# tello-encoder-generic-DaisyChain.net
KiCad netlist of a schematic drawn in EAGLE
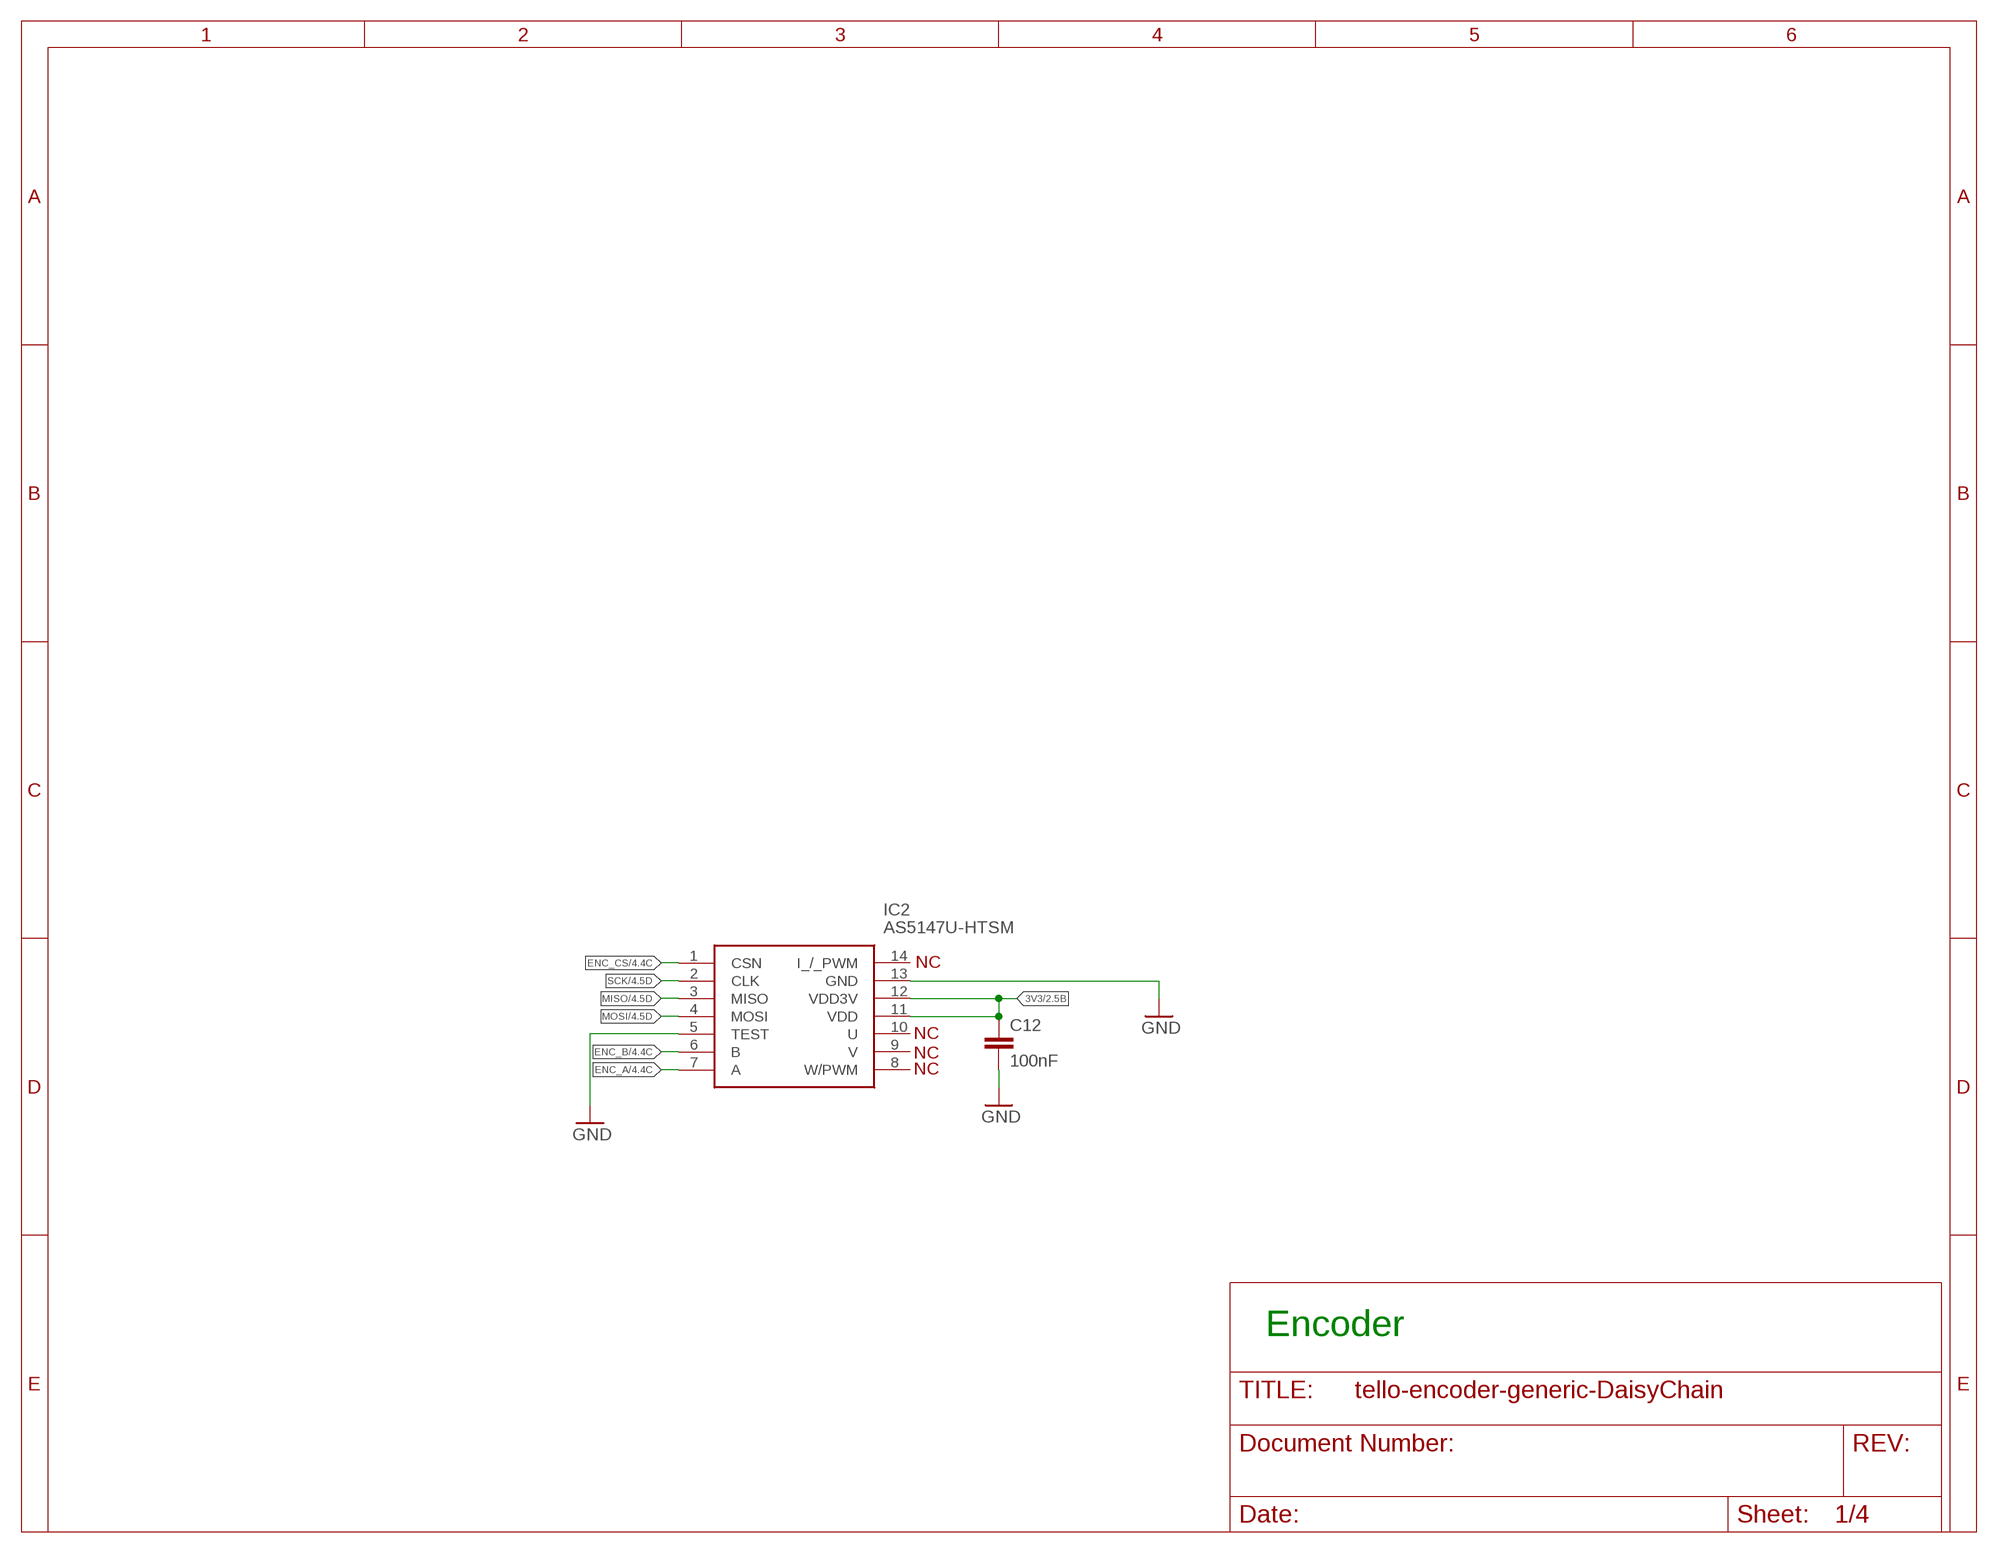
[diagram p0: schematic, sheet 1]
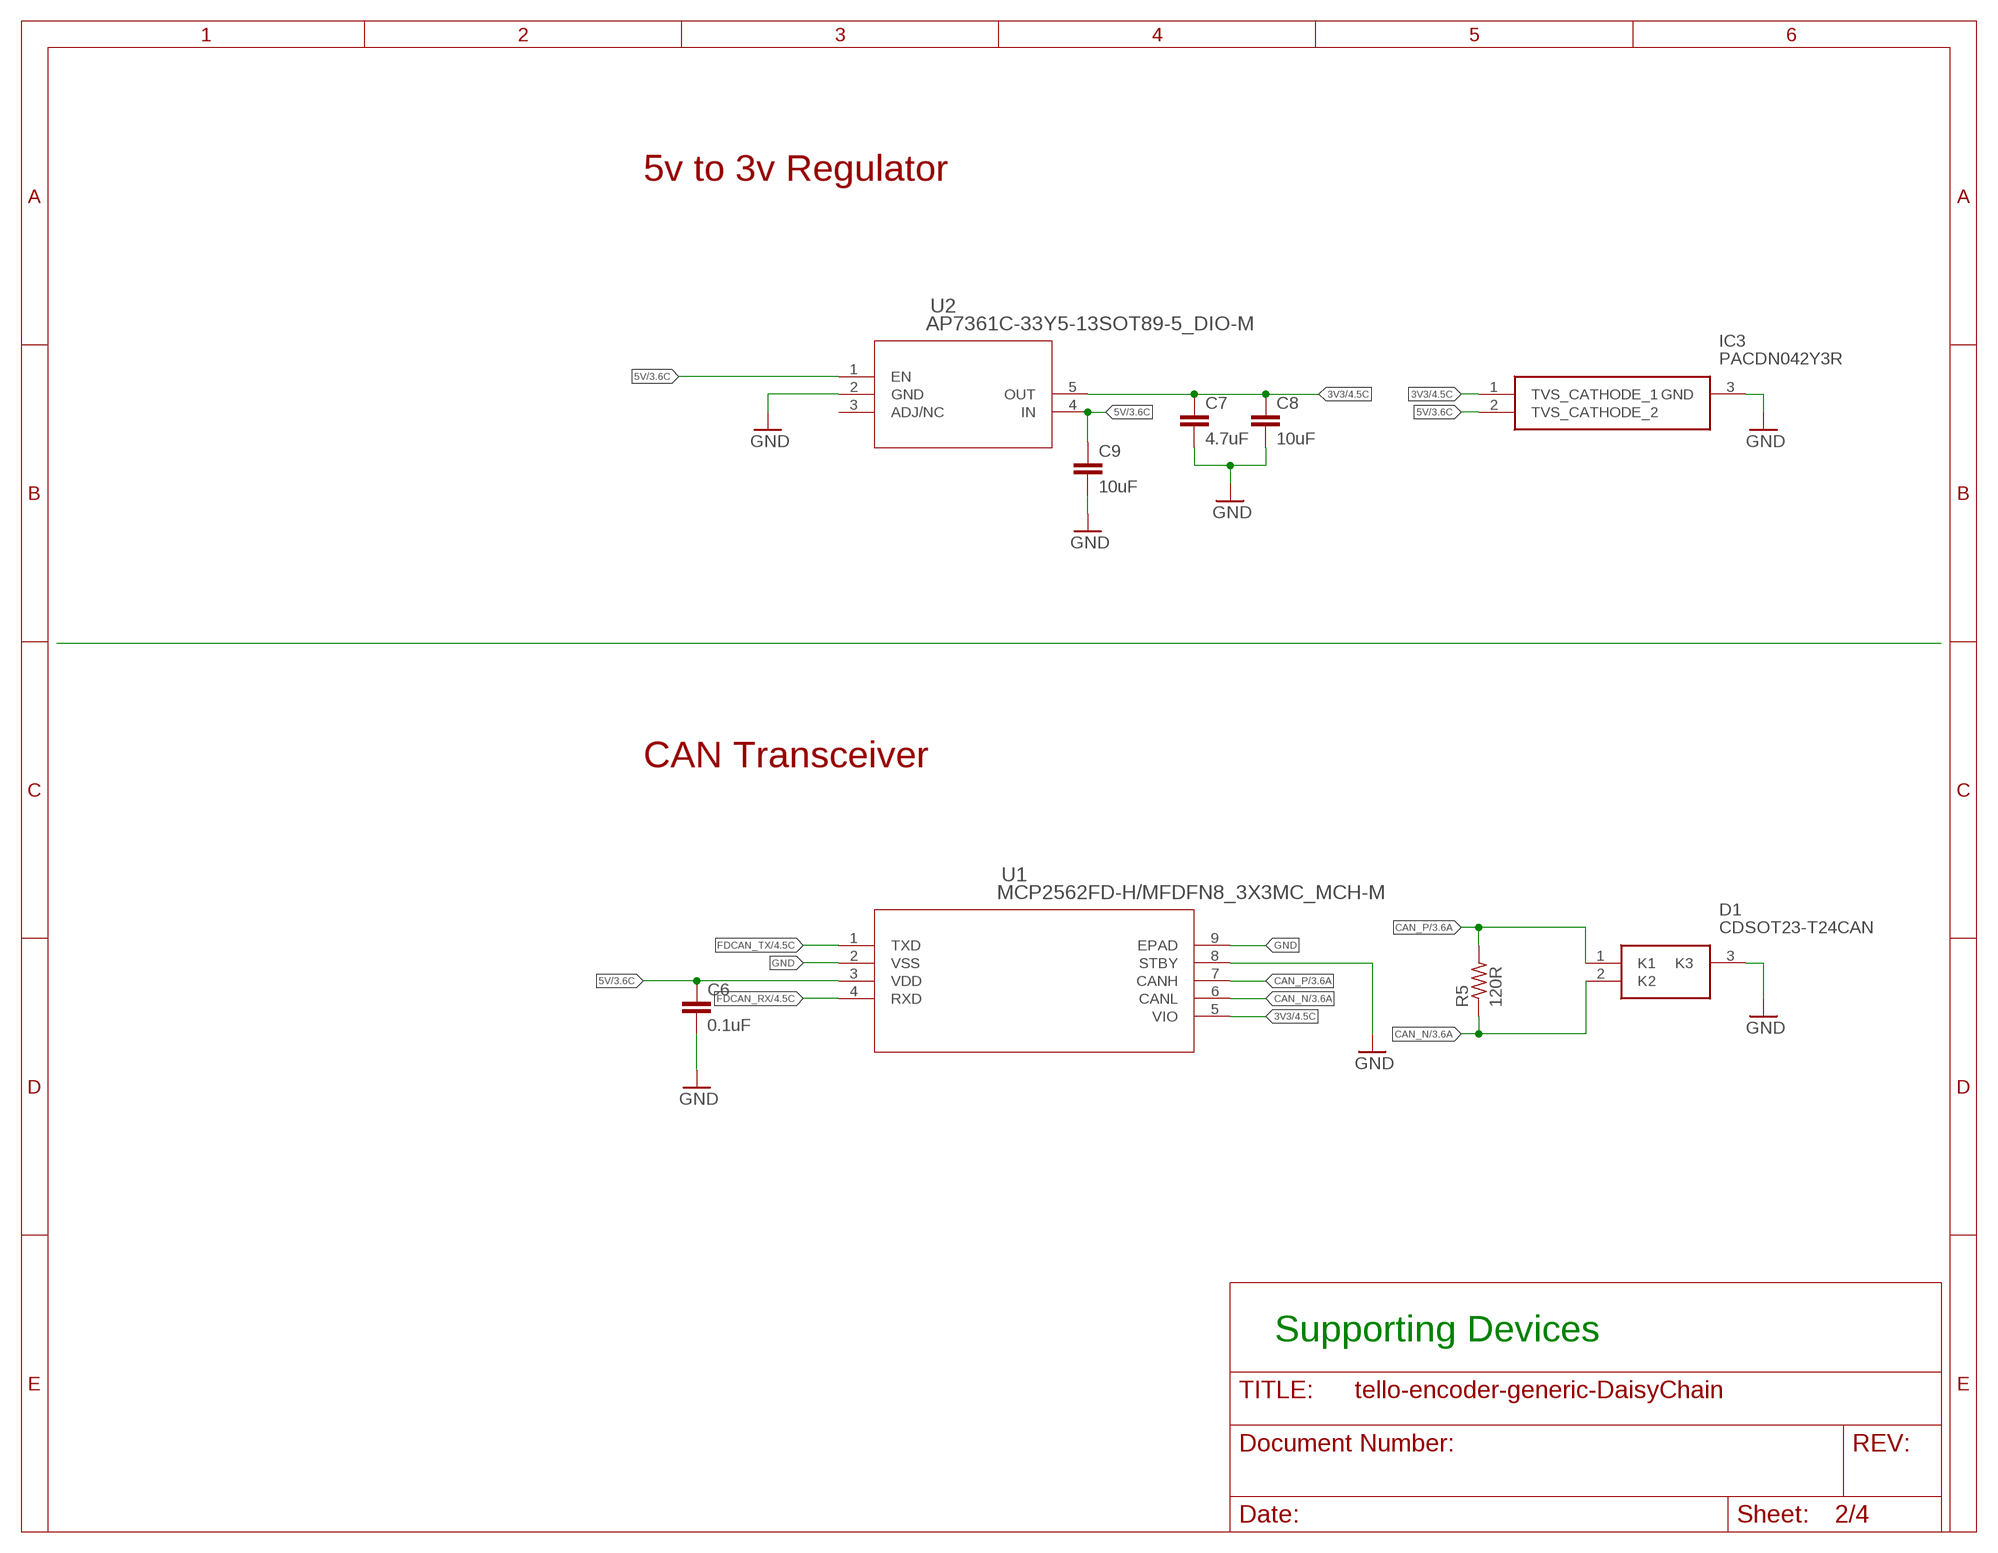
[diagram p1: schematic, sheet 2]
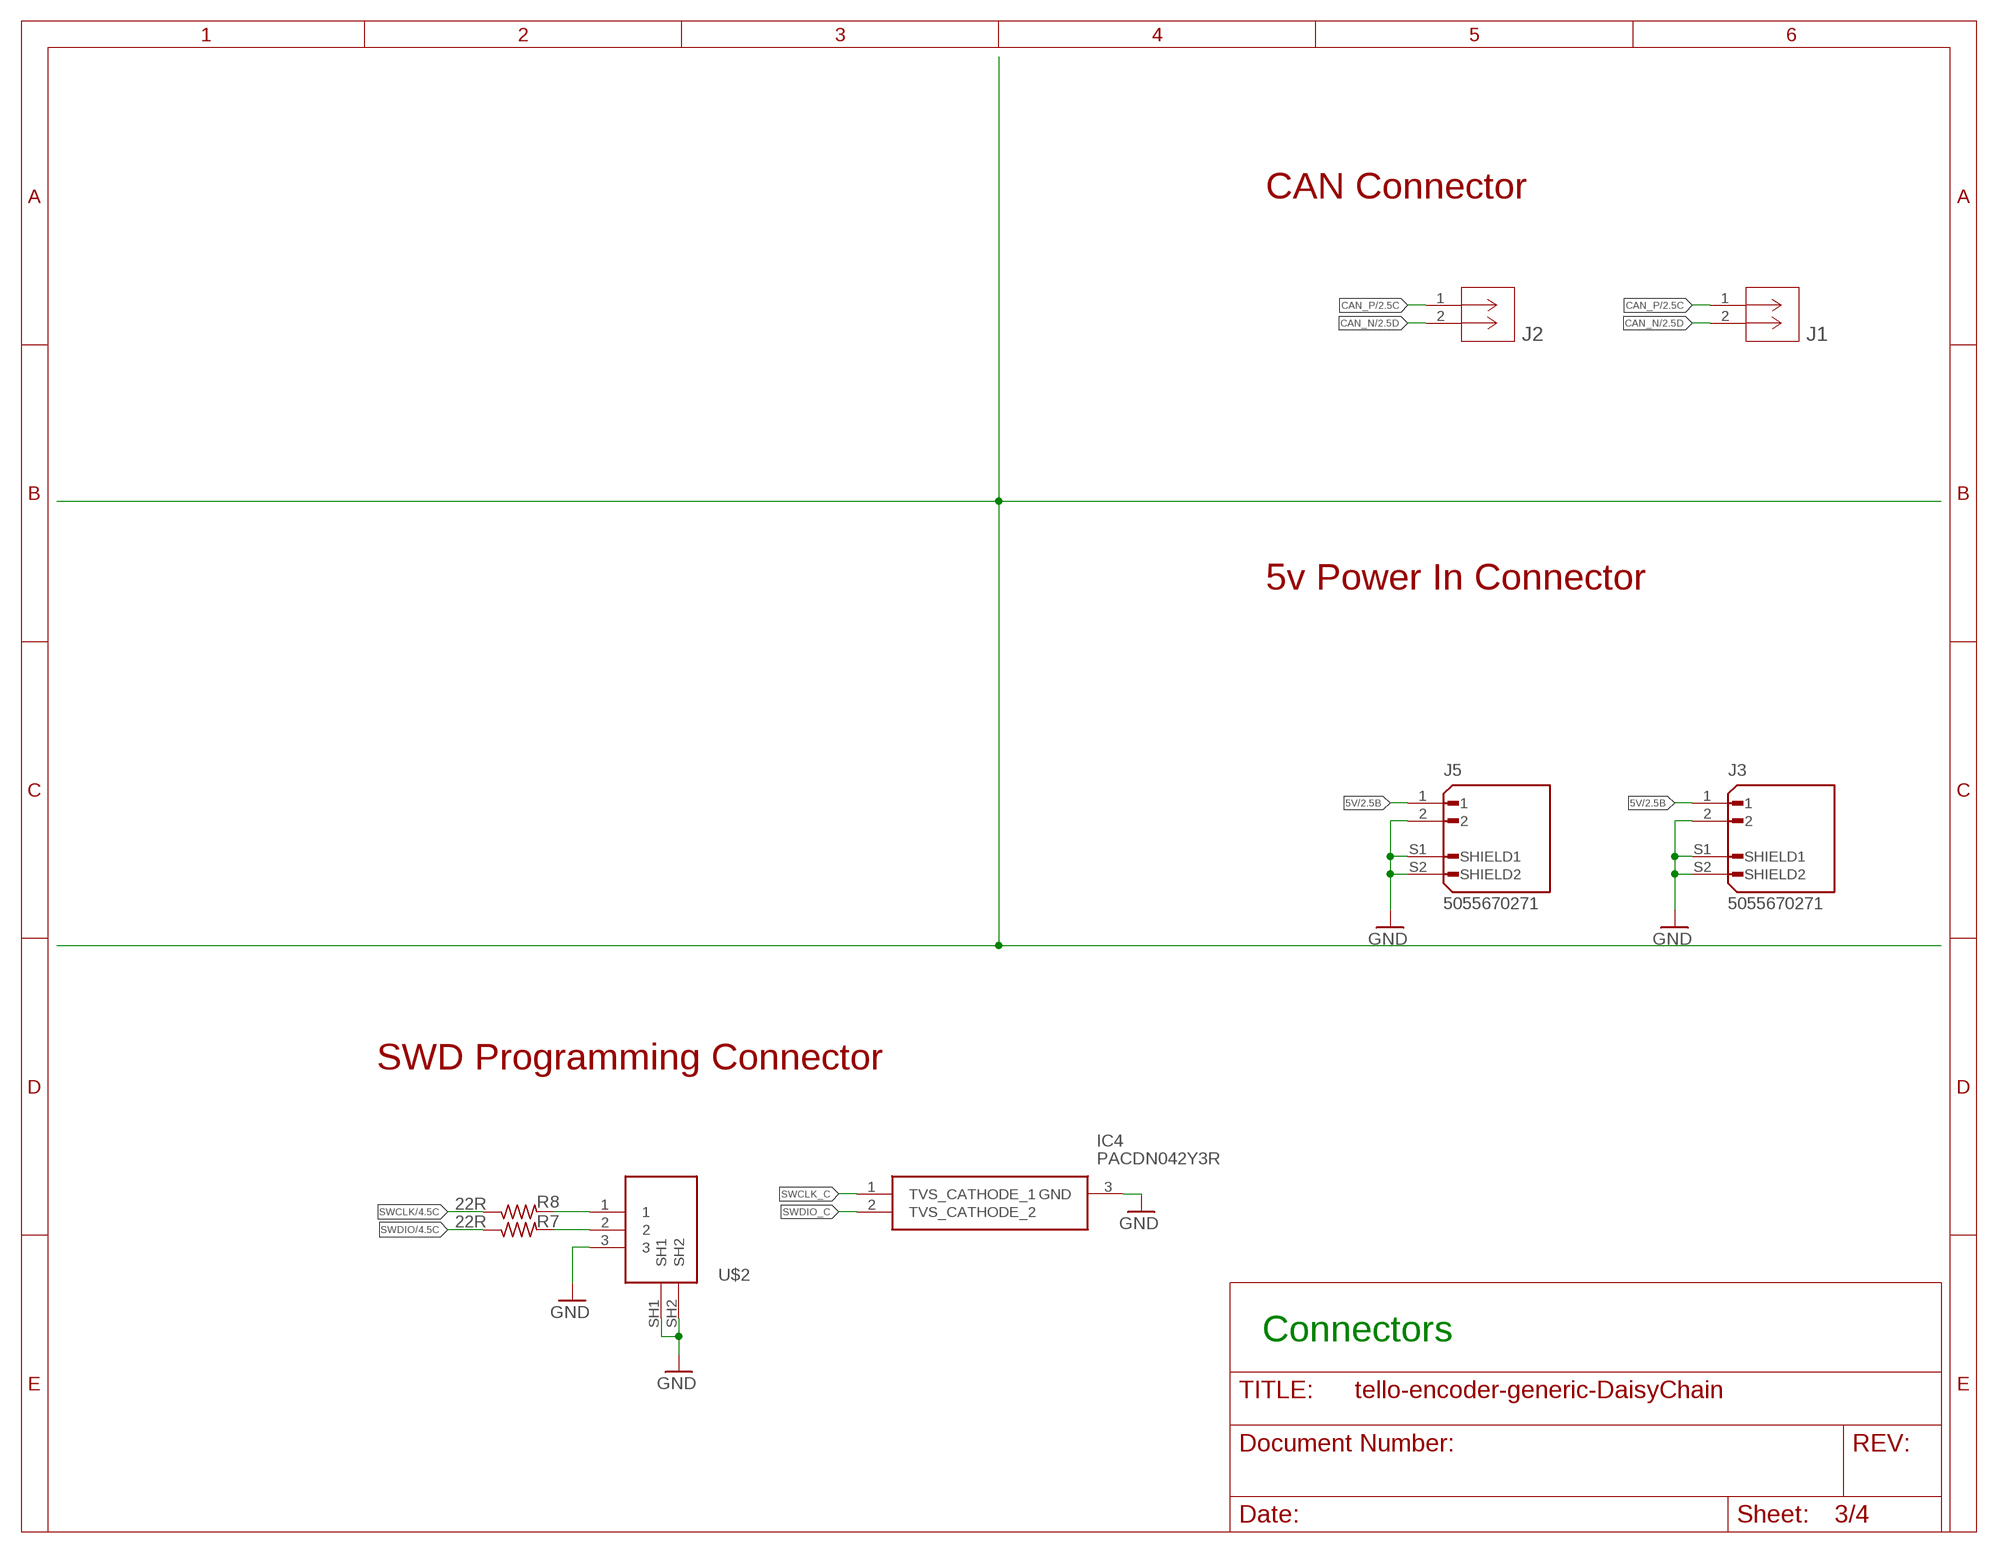
[diagram p2: schematic, sheet 3]
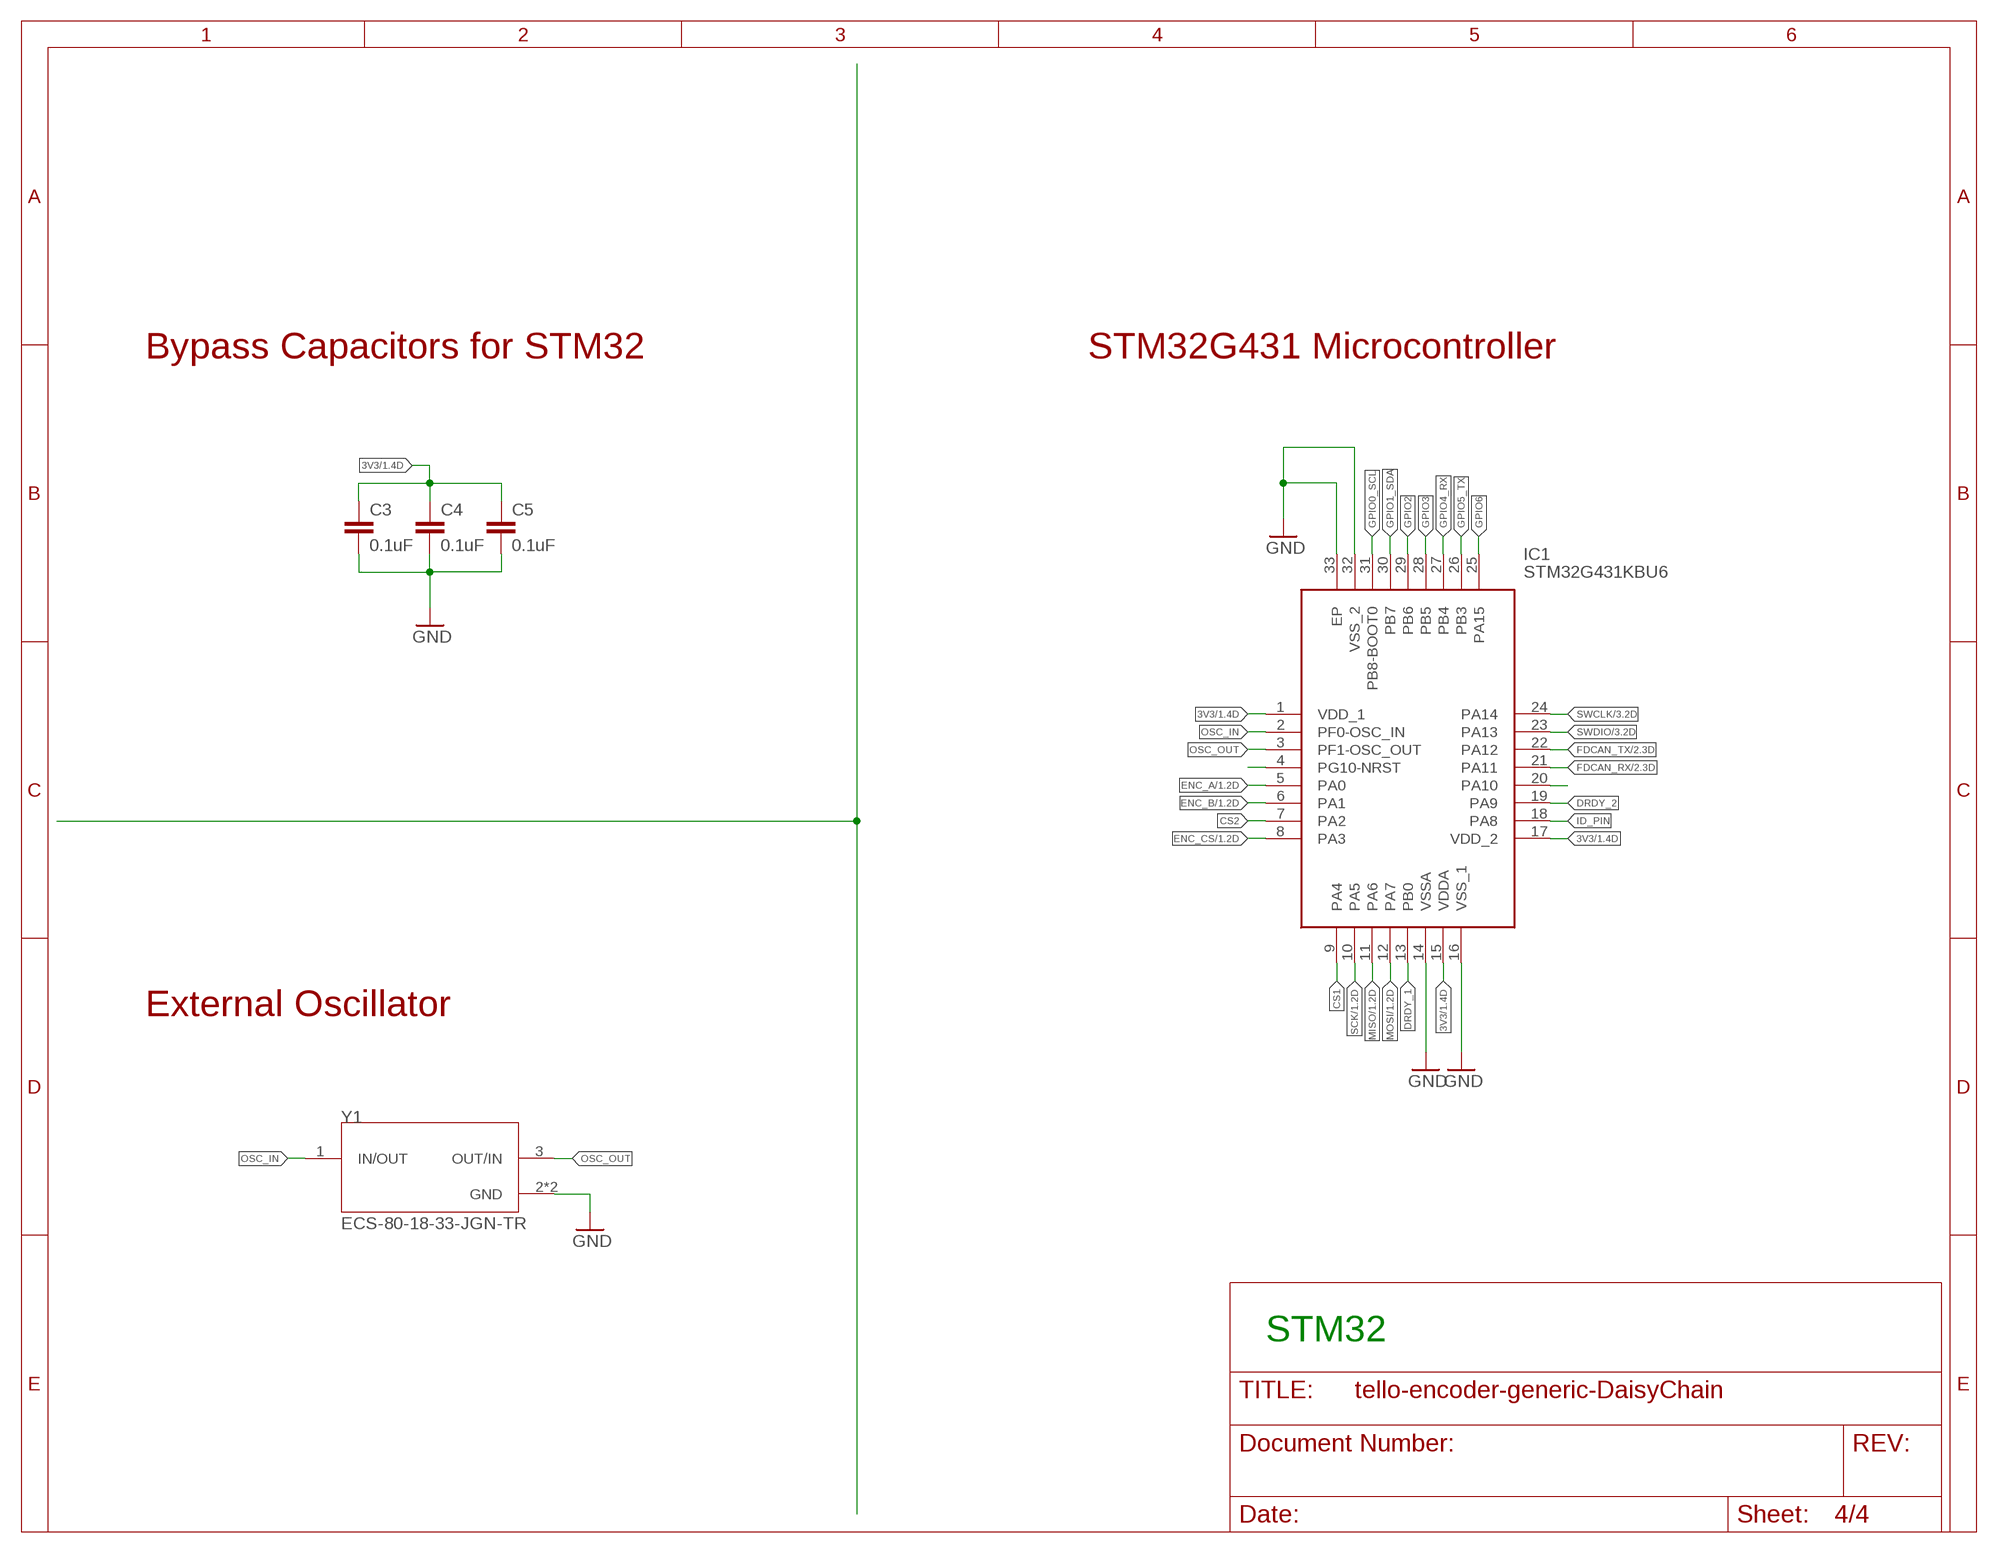
[diagram p3: schematic, sheet 4]

(export (version "E")
  (design (tool "Eeschema 10.0.6"))
  (components
    (comp (ref "C3")
      (value "0.1uF")
      (footprint "eagle-import:C0402")
      (libsource (lib "eagle-import") (part "C-EUC0402"))
    )
    (comp (ref "C4")
      (value "0.1uF")
      (footprint "eagle-import:C0402")
      (libsource (lib "eagle-import") (part "C-EUC0402"))
    )
    (comp (ref "C5")
      (value "0.1uF")
      (footprint "eagle-import:C0402")
      (libsource (lib "eagle-import") (part "C-EUC0402"))
    )
    (comp (ref "IC1")
      (value "STM32G431KBU6")
      (footprint "eagle-import:QFN50P500X500X60-33N")
      (fields (field (name "MOUSER_PART_NUMBER") "511-STM32G431KBU6"))
      (libsource (lib "eagle-import") (part "STM32G431KBU6"))
    )
    (comp (ref "Y1")
      (value "ECS-80-18-33-JGN-TR")
      (footprint "eagle-import:XTAL_ECS-240-8-33-AGN-TR")
      (fields (field (name "MF") "ECS INC") (field (name "MP") "ECX-32"))
      (libsource (lib "eagle-import") (part "ECS-80-18-33-JGN-TR"))
    )
    (comp (ref "C6")
      (value "0.1uF")
      (footprint "eagle-import:C0603")
      (libsource (lib "eagle-import") (part "C-EUC0603"))
    )
    (comp (ref "C7")
      (value "4.7uF")
      (footprint "eagle-import:C0603")
      (libsource (lib "eagle-import") (part "C-EUC0603"))
    )
    (comp (ref "C8")
      (value "10uF")
      (footprint "eagle-import:C0603")
      (libsource (lib "eagle-import") (part "C-EUC0603"))
    )
    (comp (ref "C9")
      (value "10uF")
      (footprint "eagle-import:C0603")
      (libsource (lib "eagle-import") (part "C-EUC0603"))
    )
    (comp (ref "D1")
      (value "CDSOT23-T24CAN")
      (footprint "eagle-import:SOT95P230X117-3N")
      (fields (field (name "MOUSER_PART_NUMBER") "652-CDSOT23-T24CAN"))
      (libsource (lib "eagle-import") (part "CDSOT23-T24CAN"))
    )
    (comp (ref "IC3")
      (value "PACDN042Y3R")
      (footprint "eagle-import:SOT96P237X111-3N")
      (fields (field (name "MOUSER_PART_NUMBER") "748-PACDN042Y3R"))
      (libsource (lib "eagle-import") (part "PACDN042Y3R"))
    )
    (comp (ref "R5")
      (value "120R")
      (footprint "eagle-import:R0402")
      (libsource (lib "eagle-import") (part "R-US_R0402"))
    )
    (comp (ref "U1")
      (value "MCP2562FD-H/MFDFN8_3X3MC_MCH-M")
      (footprint "eagle-import:DFN8_3X3MC_MCH-M")
      (fields
        (field (name "MANUFACTURER_PART_NUMBER") "MCP2562FD-H/MF")
        (field (name "COPYRIGHT") "Copyright (C) 2023 Ultra Librarian. All rights reserved.")
      )
      (libsource (lib "eagle-import") (part "MCP2562FD-H/MFDFN8_3X3MC_MCH-M"))
    )
    (comp (ref "U2")
      (value "AP7361C-33Y5-13SOT89-5_DIO-M")
      (footprint "eagle-import:SOT89-5_DIO-M")
      (fields
        (field (name "MANUFACTURER_PART_NUMBER") "AP7361C-33Y5-13")
        (field (name "COPYRIGHT") "Copyright (C) 2023 Ultra Librarian. All rights reserved.")
      )
      (libsource (lib "eagle-import") (part "AP7361C-33Y5-13SOT89-5_DIO-M"))
    )
    (comp (ref "IC4")
      (value "PACDN042Y3R")
      (footprint "eagle-import:SOT96P237X111-3N")
      (fields (field (name "MOUSER_PART_NUMBER") "748-PACDN042Y3R"))
      (libsource (lib "eagle-import") (part "PACDN042Y3R"))
    )
    (comp (ref "J1")
      (value "SM02BGHSTBLFSN")
      (footprint "eagle-import:CONN_SM02BGHSTB_JST")
      (fields (field (name "COPYRIGHT") "Copyright (C) 2022 Ultra Librarian. All rights reserved."))
      (libsource (lib "eagle-import") (part "SM02BGHSTBLFSN"))
    )
    (comp (ref "J2")
      (value "SM02BGHSTBLFSN")
      (footprint "eagle-import:CONN_SM02BGHSTB_JST")
      (fields (field (name "COPYRIGHT") "Copyright (C) 2022 Ultra Librarian. All rights reserved."))
      (libsource (lib "eagle-import") (part "SM02BGHSTBLFSN"))
    )
    (comp (ref "J3")
      (value "5055670271")
      (footprint "eagle-import:MOLEX_5055670271")
      (fields (field (name "MANUFACTURER") "Molex"))
      (libsource (lib "eagle-import") (part "5055670271"))
    )
    (comp (ref "J5")
      (value "5055670271")
      (footprint "eagle-import:MOLEX_5055670271")
      (fields (field (name "MANUFACTURER") "Molex"))
      (libsource (lib "eagle-import") (part "5055670271"))
    )
    (comp (ref "R7")
      (value "22R")
      (footprint "eagle-import:R0402")
      (libsource (lib "eagle-import") (part "R-US_R0402"))
    )
    (comp (ref "R8")
      (value "22R")
      (footprint "eagle-import:R0402")
      (libsource (lib "eagle-import") (part "R-US_R0402"))
    )
    (comp (ref "U$2")
      (value "125SH-G-03-TR-SMT")
      (footprint "eagle-import:125SH-G-03-TR-SMT")
      (libsource (lib "eagle-import") (part "125SH-G-03-TR-SMT"))
    )
    (comp (ref "C12")
      (value "100nF")
      (footprint "eagle-import:C0402")
      (libsource (lib "eagle-import") (part "C-EUC0402"))
    )
    (comp (ref "IC2")
      (value "AS5147U-HTSM")
      (footprint "eagle-import:SOP65P640X120-14N")
      (fields (field (name "MOUSER_PART_NUMBER") "985-AS5147U-HTSM"))
      (libsource (lib "eagle-import") (part "AS5147U-HTSM"))
    )
  )
  (nets
    (net (code "1") (name "3V3") (class "Default")
      (node (ref "C12") (pin "1") (pinfunction "1_1") (pintype "passive"))
      (node (ref "C3") (pin "1") (pinfunction "1_1") (pintype "passive"))
      (node (ref "C4") (pin "1") (pinfunction "1_1") (pintype "passive"))
      (node (ref "C5") (pin "1") (pinfunction "1_1") (pintype "passive"))
      (node (ref "C7") (pin "1") (pinfunction "1_1") (pintype "passive"))
      (node (ref "C8") (pin "1") (pinfunction "1_1") (pintype "passive"))
      (node (ref "IC1") (pin "1") (pinfunction "VDD_1_1") (pintype "bidirectional"))
      (node (ref "IC1") (pin "15") (pinfunction "VDDA_15") (pintype "bidirectional"))
      (node (ref "IC1") (pin "17") (pinfunction "VDD_2_17") (pintype "bidirectional"))
      (node (ref "IC2") (pin "11") (pinfunction "VDD_11") (pintype "bidirectional"))
      (node (ref "IC2") (pin "12") (pinfunction "VDD3V_12") (pintype "bidirectional"))
      (node (ref "IC3") (pin "1") (pinfunction "TVS_CATHODE_1_1") (pintype "bidirectional"))
      (node (ref "U1") (pin "5") (pinfunction "VIO_5") (pintype "passive"))
      (node (ref "U2") (pin "5") (pinfunction "OUT_5") (pintype "power_in"))
    )
    (net (code "2") (name "5V") (class "Default")
      (node (ref "C6") (pin "1") (pinfunction "1_1") (pintype "passive"))
      (node (ref "C9") (pin "1") (pinfunction "1_1") (pintype "passive"))
      (node (ref "IC3") (pin "2") (pinfunction "TVS_CATHODE_2_2") (pintype "bidirectional"))
      (node (ref "J3") (pin "1") (pinfunction "1_1") (pintype "passive"))
      (node (ref "J5") (pin "1") (pinfunction "1_1") (pintype "passive"))
      (node (ref "U1") (pin "3") (pinfunction "VDD_3") (pintype "power_in"))
      (node (ref "U2") (pin "1") (pinfunction "EN_1") (pintype "input"))
      (node (ref "U2") (pin "4") (pinfunction "IN_4") (pintype "power_in"))
    )
    (net (code "3") (name "CAN_N") (class "Default")
      (node (ref "D1") (pin "2") (pinfunction "K2_2") (pintype "bidirectional"))
      (node (ref "J1") (pin "2") (pinfunction "2_2") (pintype "passive"))
      (node (ref "J2") (pin "2") (pinfunction "2_2") (pintype "passive"))
      (node (ref "R5") (pin "1") (pinfunction "1_1") (pintype "passive"))
      (node (ref "U1") (pin "6") (pinfunction "CANL_6") (pintype "bidirectional"))
    )
    (net (code "4") (name "CAN_P") (class "Default")
      (node (ref "D1") (pin "1") (pinfunction "K1_1") (pintype "bidirectional"))
      (node (ref "J1") (pin "1") (pinfunction "1_1") (pintype "passive"))
      (node (ref "J2") (pin "1") (pinfunction "1_1") (pintype "passive"))
      (node (ref "R5") (pin "2") (pinfunction "2_2") (pintype "passive"))
      (node (ref "U1") (pin "7") (pinfunction "CANH_7") (pintype "bidirectional"))
    )
    (net (code "5") (name "CS1") (class "Default")
      (node (ref "IC1") (pin "9") (pinfunction "PA4_9") (pintype "bidirectional"))
    )
    (net (code "6") (name "CS2") (class "Default")
      (node (ref "IC1") (pin "7") (pinfunction "PA2_7") (pintype "bidirectional"))
    )
    (net (code "7") (name "DRDY_1") (class "Default")
      (node (ref "IC1") (pin "13") (pinfunction "PB0_13") (pintype "bidirectional"))
    )
    (net (code "8") (name "DRDY_2") (class "Default")
      (node (ref "IC1") (pin "19") (pinfunction "PA9_19") (pintype "bidirectional"))
    )
    (net (code "9") (name "ENC_A") (class "Default")
      (node (ref "IC1") (pin "5") (pinfunction "PA0_5") (pintype "bidirectional"))
      (node (ref "IC2") (pin "7") (pinfunction "A_7") (pintype "bidirectional"))
    )
    (net (code "10") (name "ENC_B") (class "Default")
      (node (ref "IC1") (pin "6") (pinfunction "PA1_6") (pintype "bidirectional"))
      (node (ref "IC2") (pin "6") (pinfunction "B_6") (pintype "bidirectional"))
    )
    (net (code "11") (name "ENC_CS") (class "Default")
      (node (ref "IC1") (pin "8") (pinfunction "PA3_8") (pintype "bidirectional"))
      (node (ref "IC2") (pin "1") (pinfunction "CSN_1") (pintype "bidirectional"))
    )
    (net (code "12") (name "FDCAN_RX") (class "Default")
      (node (ref "IC1") (pin "21") (pinfunction "PA11_21") (pintype "bidirectional"))
      (node (ref "U1") (pin "4") (pinfunction "RXD_4") (pintype "output"))
    )
    (net (code "13") (name "FDCAN_TX") (class "Default")
      (node (ref "IC1") (pin "22") (pinfunction "PA12_22") (pintype "bidirectional"))
      (node (ref "U1") (pin "1") (pinfunction "TXD_1") (pintype "input"))
    )
    (net (code "14") (name "GND") (class "Default")
      (node (ref "C12") (pin "2") (pinfunction "2_2") (pintype "passive"))
      (node (ref "C3") (pin "2") (pinfunction "2_2") (pintype "passive"))
      (node (ref "C4") (pin "2") (pinfunction "2_2") (pintype "passive"))
      (node (ref "C5") (pin "2") (pinfunction "2_2") (pintype "passive"))
      (node (ref "C6") (pin "2") (pinfunction "2_2") (pintype "passive"))
      (node (ref "C7") (pin "2") (pinfunction "2_2") (pintype "passive"))
      (node (ref "C8") (pin "2") (pinfunction "2_2") (pintype "passive"))
      (node (ref "C9") (pin "2") (pinfunction "2_2") (pintype "passive"))
      (node (ref "D1") (pin "3") (pinfunction "K3_3") (pintype "bidirectional"))
      (node (ref "IC1") (pin "14") (pinfunction "VSSA_14") (pintype "bidirectional"))
      (node (ref "IC1") (pin "16") (pinfunction "VSS_1_16") (pintype "bidirectional"))
      (node (ref "IC1") (pin "32") (pinfunction "VSS_2_32") (pintype "bidirectional"))
      (node (ref "IC1") (pin "33") (pinfunction "EP_33") (pintype "bidirectional"))
      (node (ref "IC2") (pin "13") (pinfunction "GND_13") (pintype "bidirectional"))
      (node (ref "IC2") (pin "5") (pinfunction "TEST_5") (pintype "bidirectional"))
      (node (ref "IC3") (pin "3") (pinfunction "GND_3") (pintype "power_in"))
      (node (ref "IC4") (pin "3") (pinfunction "GND_3") (pintype "power_in"))
      (node (ref "J3") (pin "2") (pinfunction "2_2") (pintype "passive"))
      (node (ref "J3") (pin "S1") (pinfunction "SHIELD1_S1") (pintype "passive"))
      (node (ref "J3") (pin "S2") (pinfunction "SHIELD2_S2") (pintype "passive"))
      (node (ref "J5") (pin "2") (pinfunction "2_2") (pintype "passive"))
      (node (ref "J5") (pin "S1") (pinfunction "SHIELD1_S1") (pintype "passive"))
      (node (ref "J5") (pin "S2") (pinfunction "SHIELD2_S2") (pintype "passive"))
      (node (ref "U$2") (pin "3") (pinfunction "3_3") (pintype "bidirectional"))
      (node (ref "U$2") (pin "SH1") (pinfunction "SH1_SH1") (pintype "bidirectional"))
      (node (ref "U$2") (pin "SH2") (pinfunction "SH2_SH2") (pintype "bidirectional"))
      (node (ref "U1") (pin "2") (pinfunction "VSS_2") (pintype "power_in"))
      (node (ref "U1") (pin "8") (pinfunction "STBY_8") (pintype "input"))
      (node (ref "U1") (pin "9") (pinfunction "EPAD_9") (pintype "passive"))
      (node (ref "U2") (pin "2") (pinfunction "GND_2") (pintype "passive"))
      (node (ref "Y1") (pin "2") (pinfunction "GND_2") (pintype "power_in"))
      (node (ref "Y1") (pin "4") (pinfunction "GND_4") (pintype "power_in"))
    )
    (net (code "15") (name "GPIO0_SCL") (class "Default")
      (node (ref "IC1") (pin "31") (pinfunction "PB8-BOOT0_31") (pintype "bidirectional"))
    )
    (net (code "16") (name "GPIO1_SDA") (class "Default")
      (node (ref "IC1") (pin "30") (pinfunction "PB7_30") (pintype "bidirectional"))
    )
    (net (code "17") (name "GPIO2") (class "Default")
      (node (ref "IC1") (pin "29") (pinfunction "PB6_29") (pintype "bidirectional"))
    )
    (net (code "18") (name "GPIO3") (class "Default")
      (node (ref "IC1") (pin "28") (pinfunction "PB5_28") (pintype "bidirectional"))
    )
    (net (code "19") (name "GPIO4_RX") (class "Default")
      (node (ref "IC1") (pin "27") (pinfunction "PB4_27") (pintype "bidirectional"))
    )
    (net (code "20") (name "GPIO5_TX") (class "Default")
      (node (ref "IC1") (pin "26") (pinfunction "PB3_26") (pintype "bidirectional"))
    )
    (net (code "21") (name "GPIO6") (class "Default")
      (node (ref "IC1") (pin "25") (pinfunction "PA15_25") (pintype "bidirectional"))
    )
    (net (code "22") (name "ID_PIN") (class "Default")
      (node (ref "IC1") (pin "18") (pinfunction "PA8_18") (pintype "bidirectional"))
    )
    (net (code "23") (name "MISO") (class "Default")
      (node (ref "IC1") (pin "11") (pinfunction "PA6_11") (pintype "bidirectional"))
      (node (ref "IC2") (pin "3") (pinfunction "MISO_3") (pintype "bidirectional"))
    )
    (net (code "24") (name "MOSI") (class "Default")
      (node (ref "IC1") (pin "12") (pinfunction "PA7_12") (pintype "bidirectional"))
      (node (ref "IC2") (pin "4") (pinfunction "MOSI_4") (pintype "bidirectional"))
    )
    (net (code "25") (name "OSC_IN") (class "Default")
      (node (ref "IC1") (pin "2") (pinfunction "PF0-OSC_IN_2") (pintype "bidirectional"))
      (node (ref "Y1") (pin "1") (pinfunction "IN/OUT_1") (pintype "bidirectional"))
    )
    (net (code "26") (name "OSC_OUT") (class "Default")
      (node (ref "IC1") (pin "3") (pinfunction "PF1-OSC_OUT_3") (pintype "bidirectional"))
      (node (ref "Y1") (pin "3") (pinfunction "OUT/IN_3") (pintype "bidirectional"))
    )
    (net (code "27") (name "SCK") (class "Default")
      (node (ref "IC1") (pin "10") (pinfunction "PA5_10") (pintype "bidirectional"))
      (node (ref "IC2") (pin "2") (pinfunction "CLK_2") (pintype "bidirectional"))
    )
    (net (code "28") (name "SWCLK") (class "Default")
      (node (ref "IC1") (pin "24") (pinfunction "PA14_24") (pintype "bidirectional"))
      (node (ref "R8") (pin "1") (pinfunction "1_1") (pintype "passive"))
    )
    (net (code "29") (name "SWCLK_C") (class "Default")
      (node (ref "IC4") (pin "1") (pinfunction "TVS_CATHODE_1_1") (pintype "bidirectional"))
      (node (ref "R8") (pin "2") (pinfunction "2_2") (pintype "passive"))
      (node (ref "U$2") (pin "1") (pinfunction "1_1") (pintype "bidirectional"))
    )
    (net (code "30") (name "SWDIO") (class "Default")
      (node (ref "IC1") (pin "23") (pinfunction "PA13_23") (pintype "bidirectional"))
      (node (ref "R7") (pin "1") (pinfunction "1_1") (pintype "passive"))
    )
    (net (code "31") (name "SWDIO_C") (class "Default")
      (node (ref "IC4") (pin "2") (pinfunction "TVS_CATHODE_2_2") (pintype "bidirectional"))
      (node (ref "R7") (pin "2") (pinfunction "2_2") (pintype "passive"))
      (node (ref "U$2") (pin "2") (pinfunction "2_2") (pintype "bidirectional"))
    )
    (net (code "32") (name "unconnected-(IC1-PA10-Pad20)") (class "Default")
      (node (ref "IC1") (pin "20") (pinfunction "PA10_20") (pintype "bidirectional"))
    )
    (net (code "33") (name "unconnected-(IC1-PG10-NRST-Pad4)") (class "Default")
      (node (ref "IC1") (pin "4") (pinfunction "PG10-NRST_4") (pintype "bidirectional"))
    )
    (net (code "34") (name "unconnected-(IC2-I_{slash}_PWM-Pad14)") (class "Default")
      (node (ref "IC2") (pin "14") (pinfunction "I_/_PWM_14") (pintype "bidirectional"))
    )
    (net (code "35") (name "unconnected-(IC2-U-Pad10)") (class "Default")
      (node (ref "IC2") (pin "10") (pinfunction "U_10") (pintype "bidirectional"))
    )
    (net (code "36") (name "unconnected-(IC2-V-Pad9)") (class "Default")
      (node (ref "IC2") (pin "9") (pinfunction "V_9") (pintype "bidirectional"))
    )
    (net (code "37") (name "unconnected-(IC2-W{slash}PWM-Pad8)") (class "Default")
      (node (ref "IC2") (pin "8") (pinfunction "W/PWM_8") (pintype "bidirectional"))
    )
    (net (code "38") (name "unconnected-(U2-ADJ{slash}NC-Pad3)") (class "Default")
      (node (ref "U2") (pin "3") (pinfunction "ADJ/NC_3") (pintype "passive"))
    )
  )
)
